# m1-program-counter.net
KiCad netlist of a schematic drawn in EAGLE
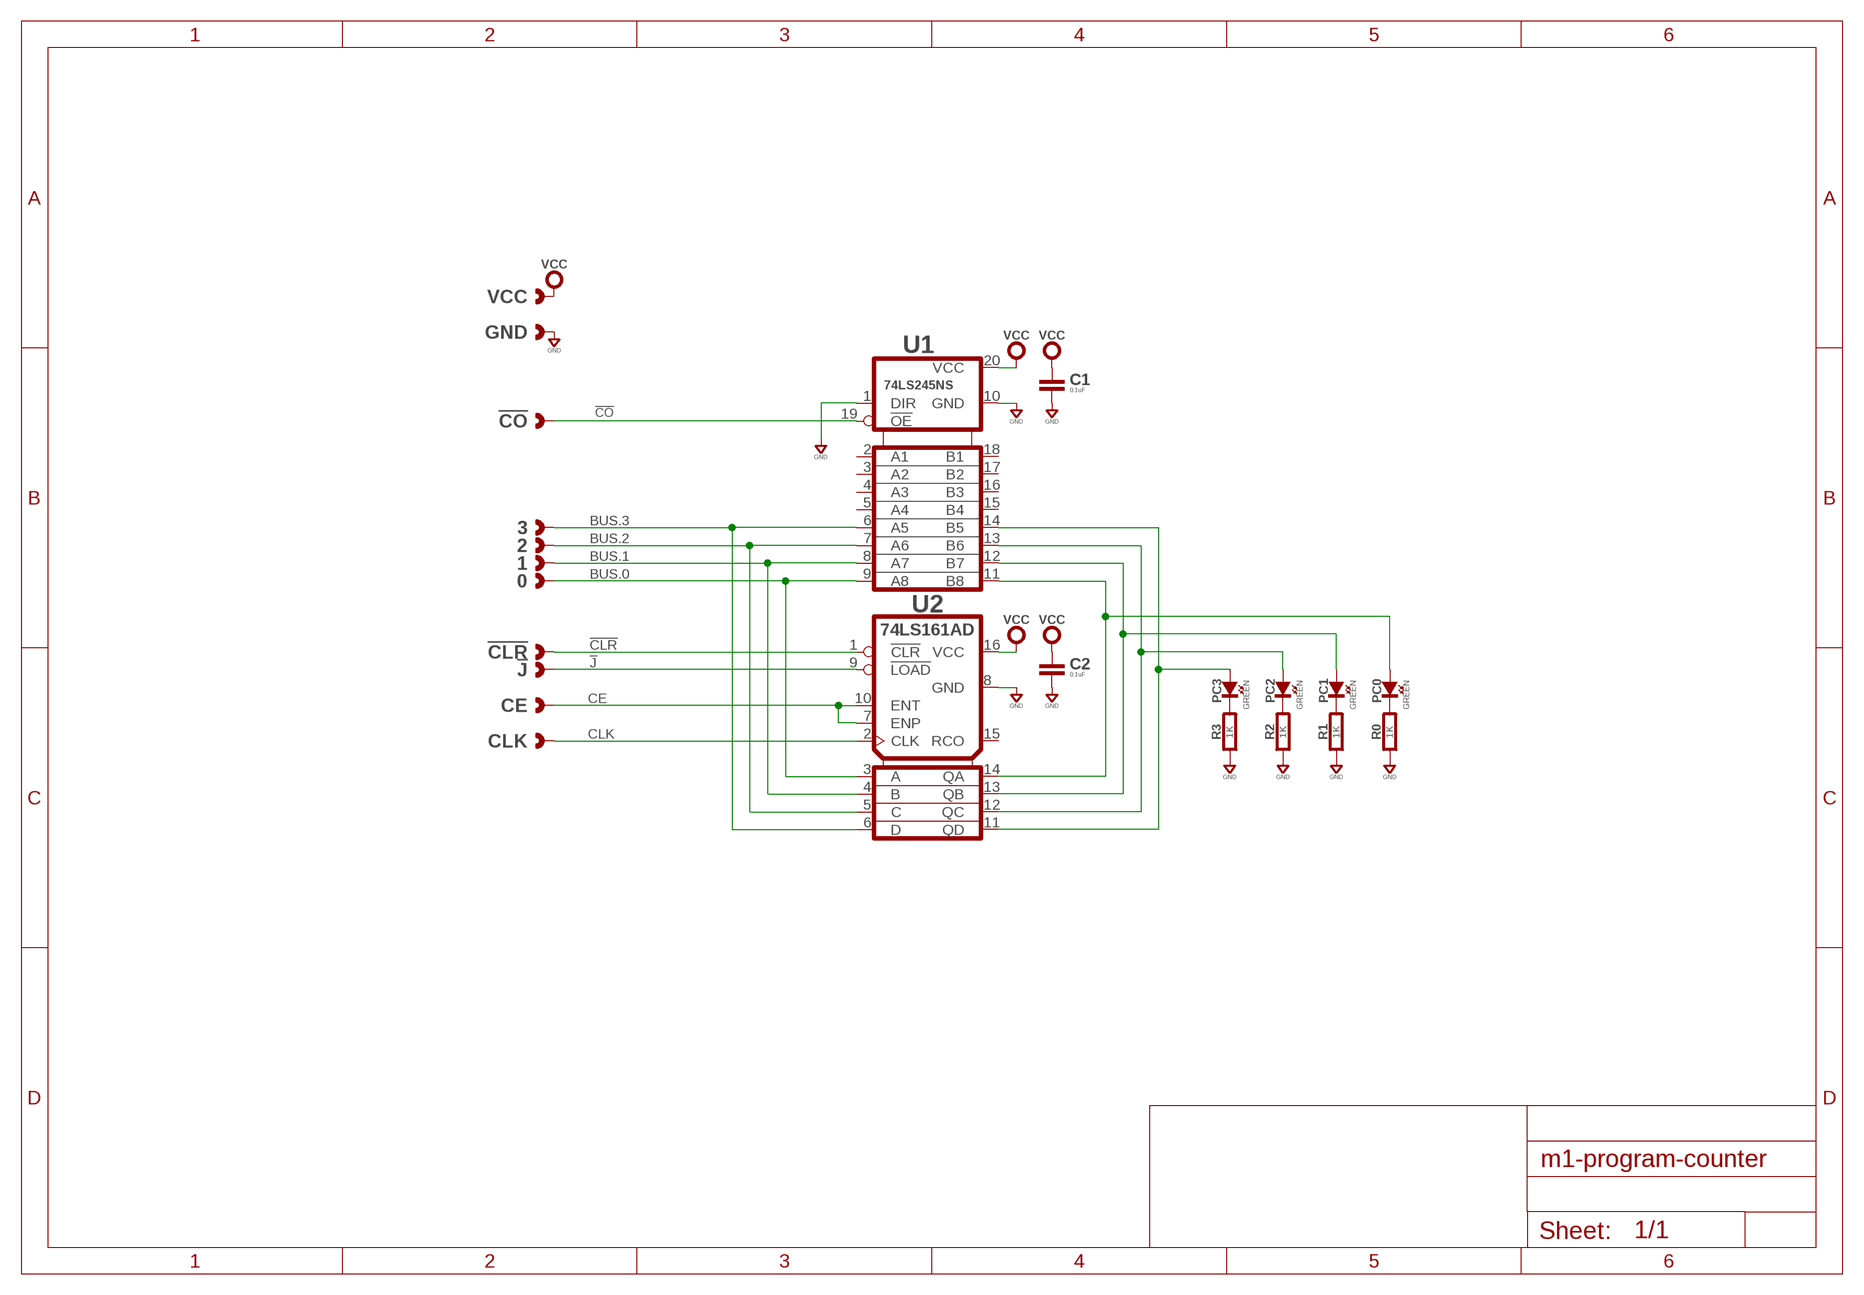
[diagram p0: schematic, sheet 1]

(export (version "E")
  (design (tool "Eeschema 10.0.6"))
  (components
    (comp (ref "!CLR")
      (value "CAST-01X1")
      (footprint "eagle-import:CAST01-2.54MM")
      (libsource (lib "eagle-import") (part "CAST-01X1"))
    )
    (comp (ref "!CO")
      (value "CAST-01X1")
      (footprint "eagle-import:CAST01-2.54MM")
      (libsource (lib "eagle-import") (part "CAST-01X1"))
    )
    (comp (ref "!J")
      (value "CAST-01X1")
      (footprint "eagle-import:CAST01-2.54MM")
      (libsource (lib "eagle-import") (part "CAST-01X1"))
    )
    (comp (ref "0")
      (value "CAST-01X1")
      (footprint "eagle-import:CAST01-2.54MM")
      (libsource (lib "eagle-import") (part "CAST-01X1"))
    )
    (comp (ref "1")
      (value "CAST-01X1")
      (footprint "eagle-import:CAST01-2.54MM")
      (libsource (lib "eagle-import") (part "CAST-01X1"))
    )
    (comp (ref "2")
      (value "CAST-01X1")
      (footprint "eagle-import:CAST01-2.54MM")
      (libsource (lib "eagle-import") (part "CAST-01X1"))
    )
    (comp (ref "3")
      (value "CAST-01X1")
      (footprint "eagle-import:CAST01-2.54MM")
      (libsource (lib "eagle-import") (part "CAST-01X1"))
    )
    (comp (ref "C1")
      (value "0.1uF")
      (footprint "eagle-import:0603-CAP")
      (libsource (lib "eagle-import") (part "CAPACITOR0603"))
    )
    (comp (ref "C2")
      (value "0.1uF")
      (footprint "eagle-import:0603-CAP")
      (libsource (lib "eagle-import") (part "CAPACITOR0603"))
    )
    (comp (ref "CE")
      (value "CAST-01X1")
      (footprint "eagle-import:CAST01-2.54MM")
      (libsource (lib "eagle-import") (part "CAST-01X1"))
    )
    (comp (ref "CLK")
      (value "CAST-01X1")
      (footprint "eagle-import:CAST01-2.54MM")
      (libsource (lib "eagle-import") (part "CAST-01X1"))
    )
    (comp (ref "GND")
      (value "CAST-01X1")
      (footprint "eagle-import:CAST01-2.54MM")
      (libsource (lib "eagle-import") (part "CAST-01X1"))
    )
    (comp (ref "PC0")
      (value "GREEN")
      (footprint "eagle-import:SMD_0603")
      (libsource (lib "eagle-import") (part "SMT0603"))
    )
    (comp (ref "PC1")
      (value "GREEN")
      (footprint "eagle-import:SMD_0603")
      (libsource (lib "eagle-import") (part "SMT0603"))
    )
    (comp (ref "PC2")
      (value "GREEN")
      (footprint "eagle-import:SMD_0603")
      (libsource (lib "eagle-import") (part "SMT0603"))
    )
    (comp (ref "PC3")
      (value "GREEN")
      (footprint "eagle-import:SMD_0603")
      (libsource (lib "eagle-import") (part "SMT0603"))
    )
    (comp (ref "R0")
      (value "1K")
      (footprint "eagle-import:0603-RES")
      (libsource (lib "eagle-import") (part "RESISTOR0603"))
    )
    (comp (ref "R1")
      (value "1K")
      (footprint "eagle-import:0603-RES")
      (libsource (lib "eagle-import") (part "RESISTOR0603"))
    )
    (comp (ref "R2")
      (value "1K")
      (footprint "eagle-import:0603-RES")
      (libsource (lib "eagle-import") (part "RESISTOR0603"))
    )
    (comp (ref "R3")
      (value "1K")
      (footprint "eagle-import:0603-RES")
      (libsource (lib "eagle-import") (part "RESISTOR0603"))
    )
    (comp (ref "U1")
      (value "74LS245NS")
      (footprint "eagle-import:SO20")
      (libsource (lib "eagle-import") (part "74245?NSLS"))
    )
    (comp (ref "U2")
      (value "74LS161AD")
      (footprint "eagle-import:SO16")
      (libsource (lib "eagle-import") (part "74161A?DLS"))
    )
    (comp (ref "VCC")
      (value "CAST-01X1")
      (footprint "eagle-import:CAST01-2.54MM")
      (libsource (lib "eagle-import") (part "CAST-01X1"))
    )
  )
  (nets
    (net (code "1") (name "/BUS.0") (class "Default")
      (node (ref "0") (pin "1") (pinfunction "1_1") (pintype "bidirectional"))
      (node (ref "U1") (pin "9") (pinfunction "A8_9") (pintype "bidirectional"))
      (node (ref "U2") (pin "3") (pinfunction "A_3") (pintype "bidirectional"))
    )
    (net (code "2") (name "/BUS.1") (class "Default")
      (node (ref "1") (pin "1") (pinfunction "1_1") (pintype "bidirectional"))
      (node (ref "U1") (pin "8") (pinfunction "A7_8") (pintype "bidirectional"))
      (node (ref "U2") (pin "4") (pinfunction "B_4") (pintype "bidirectional"))
    )
    (net (code "3") (name "/BUS.2") (class "Default")
      (node (ref "2") (pin "1") (pinfunction "1_1") (pintype "bidirectional"))
      (node (ref "U1") (pin "7") (pinfunction "A6_7") (pintype "bidirectional"))
      (node (ref "U2") (pin "5") (pinfunction "C_5") (pintype "bidirectional"))
    )
    (net (code "4") (name "/BUS.3") (class "Default")
      (node (ref "3") (pin "1") (pinfunction "1_1") (pintype "bidirectional"))
      (node (ref "U1") (pin "6") (pinfunction "A5_6") (pintype "bidirectional"))
      (node (ref "U2") (pin "6") (pinfunction "D_6") (pintype "bidirectional"))
    )
    (net (code "5") (name "/CE") (class "Default")
      (node (ref "CE") (pin "1") (pinfunction "1_1") (pintype "bidirectional"))
      (node (ref "U2") (pin "10") (pinfunction "ENT_10") (pintype "bidirectional"))
      (node (ref "U2") (pin "7") (pinfunction "ENP_7") (pintype "bidirectional"))
    )
    (net (code "6") (name "/CLK") (class "Default")
      (node (ref "CLK") (pin "1") (pinfunction "1_1") (pintype "bidirectional"))
      (node (ref "U2") (pin "2") (pinfunction "CLK_2") (pintype "bidirectional"))
    )
    (net (code "7") (name "/~{CLR}") (class "Default")
      (node (ref "!CLR") (pin "1") (pinfunction "1_1") (pintype "bidirectional"))
      (node (ref "U2") (pin "1") (pinfunction "~{CLR}_1") (pintype "bidirectional"))
    )
    (net (code "8") (name "/~{CO}") (class "Default")
      (node (ref "!CO") (pin "1") (pinfunction "1_1") (pintype "bidirectional"))
      (node (ref "U1") (pin "19") (pinfunction "~{OE}_19") (pintype "bidirectional"))
    )
    (net (code "9") (name "/~{J}") (class "Default")
      (node (ref "!J") (pin "1") (pinfunction "1_1") (pintype "bidirectional"))
      (node (ref "U2") (pin "9") (pinfunction "~{LOAD}_9") (pintype "bidirectional"))
    )
    (net (code "10") (name "GND") (class "Default")
      (node (ref "C1") (pin "2") (pinfunction "2_2") (pintype "passive"))
      (node (ref "C2") (pin "2") (pinfunction "2_2") (pintype "passive"))
      (node (ref "GND") (pin "1") (pinfunction "1_1") (pintype "bidirectional"))
      (node (ref "R0") (pin "1") (pinfunction "1_1") (pintype "passive"))
      (node (ref "R1") (pin "1") (pinfunction "1_1") (pintype "passive"))
      (node (ref "R2") (pin "1") (pinfunction "1_1") (pintype "passive"))
      (node (ref "R3") (pin "1") (pinfunction "1_1") (pintype "passive"))
      (node (ref "U1") (pin "1") (pinfunction "DIR_1") (pintype "bidirectional"))
      (node (ref "U1") (pin "10") (pinfunction "GND_10") (pintype "bidirectional"))
      (node (ref "U2") (pin "8") (pinfunction "GND_8") (pintype "bidirectional"))
    )
    (net (code "11") (name "Net-(PC0-C)") (class "Default")
      (node (ref "PC0") (pin "K") (pinfunction "C_K") (pintype "passive"))
      (node (ref "R0") (pin "2") (pinfunction "2_2") (pintype "passive"))
    )
    (net (code "12") (name "Net-(PC1-C)") (class "Default")
      (node (ref "PC1") (pin "K") (pinfunction "C_K") (pintype "passive"))
      (node (ref "R1") (pin "2") (pinfunction "2_2") (pintype "passive"))
    )
    (net (code "13") (name "Net-(PC2-C)") (class "Default")
      (node (ref "PC2") (pin "K") (pinfunction "C_K") (pintype "passive"))
      (node (ref "R2") (pin "2") (pinfunction "2_2") (pintype "passive"))
    )
    (net (code "14") (name "Net-(PC3-C)") (class "Default")
      (node (ref "PC3") (pin "K") (pinfunction "C_K") (pintype "passive"))
      (node (ref "R3") (pin "2") (pinfunction "2_2") (pintype "passive"))
    )
    (net (code "15") (name "Net-(U1-B5)") (class "Default")
      (node (ref "PC3") (pin "A") (pinfunction "A_A") (pintype "passive"))
      (node (ref "U1") (pin "14") (pinfunction "B5_14") (pintype "bidirectional"))
      (node (ref "U2") (pin "11") (pinfunction "QD_11") (pintype "bidirectional"))
    )
    (net (code "16") (name "Net-(U1-B6)") (class "Default")
      (node (ref "PC2") (pin "A") (pinfunction "A_A") (pintype "passive"))
      (node (ref "U1") (pin "13") (pinfunction "B6_13") (pintype "bidirectional"))
      (node (ref "U2") (pin "12") (pinfunction "QC_12") (pintype "bidirectional"))
    )
    (net (code "17") (name "Net-(U1-B7)") (class "Default")
      (node (ref "PC1") (pin "A") (pinfunction "A_A") (pintype "passive"))
      (node (ref "U1") (pin "12") (pinfunction "B7_12") (pintype "bidirectional"))
      (node (ref "U2") (pin "13") (pinfunction "QB_13") (pintype "bidirectional"))
    )
    (net (code "18") (name "Net-(U1-B8)") (class "Default")
      (node (ref "PC0") (pin "A") (pinfunction "A_A") (pintype "passive"))
      (node (ref "U1") (pin "11") (pinfunction "B8_11") (pintype "bidirectional"))
      (node (ref "U2") (pin "14") (pinfunction "QA_14") (pintype "bidirectional"))
    )
    (net (code "19") (name "VCC") (class "Default")
      (node (ref "C1") (pin "1") (pinfunction "1_1") (pintype "passive"))
      (node (ref "C2") (pin "1") (pinfunction "1_1") (pintype "passive"))
      (node (ref "U1") (pin "20") (pinfunction "VCC_20") (pintype "bidirectional"))
      (node (ref "U2") (pin "16") (pinfunction "VCC_16") (pintype "bidirectional"))
      (node (ref "VCC") (pin "1") (pinfunction "1_1") (pintype "bidirectional"))
    )
    (net (code "20") (name "unconnected-(U1-A1-Pad2)") (class "Default")
      (node (ref "U1") (pin "2") (pinfunction "A1_2") (pintype "bidirectional"))
    )
    (net (code "21") (name "unconnected-(U1-A2-Pad3)") (class "Default")
      (node (ref "U1") (pin "3") (pinfunction "A2_3") (pintype "bidirectional"))
    )
    (net (code "22") (name "unconnected-(U1-A3-Pad4)") (class "Default")
      (node (ref "U1") (pin "4") (pinfunction "A3_4") (pintype "bidirectional"))
    )
    (net (code "23") (name "unconnected-(U1-A4-Pad5)") (class "Default")
      (node (ref "U1") (pin "5") (pinfunction "A4_5") (pintype "bidirectional"))
    )
    (net (code "24") (name "unconnected-(U1-B1-Pad18)") (class "Default")
      (node (ref "U1") (pin "18") (pinfunction "B1_18") (pintype "bidirectional"))
    )
    (net (code "25") (name "unconnected-(U1-B2-Pad17)") (class "Default")
      (node (ref "U1") (pin "17") (pinfunction "B2_17") (pintype "bidirectional"))
    )
    (net (code "26") (name "unconnected-(U1-B3-Pad16)") (class "Default")
      (node (ref "U1") (pin "16") (pinfunction "B3_16") (pintype "bidirectional"))
    )
    (net (code "27") (name "unconnected-(U1-B4-Pad15)") (class "Default")
      (node (ref "U1") (pin "15") (pinfunction "B4_15") (pintype "bidirectional"))
    )
    (net (code "28") (name "unconnected-(U2-RCO-Pad15)") (class "Default")
      (node (ref "U2") (pin "15") (pinfunction "RCO_15") (pintype "bidirectional"))
    )
  )
)
